# SCH_555-Circuit_2025-03-22_1.net
KiCad netlist of a schematic drawn in EasyEDA
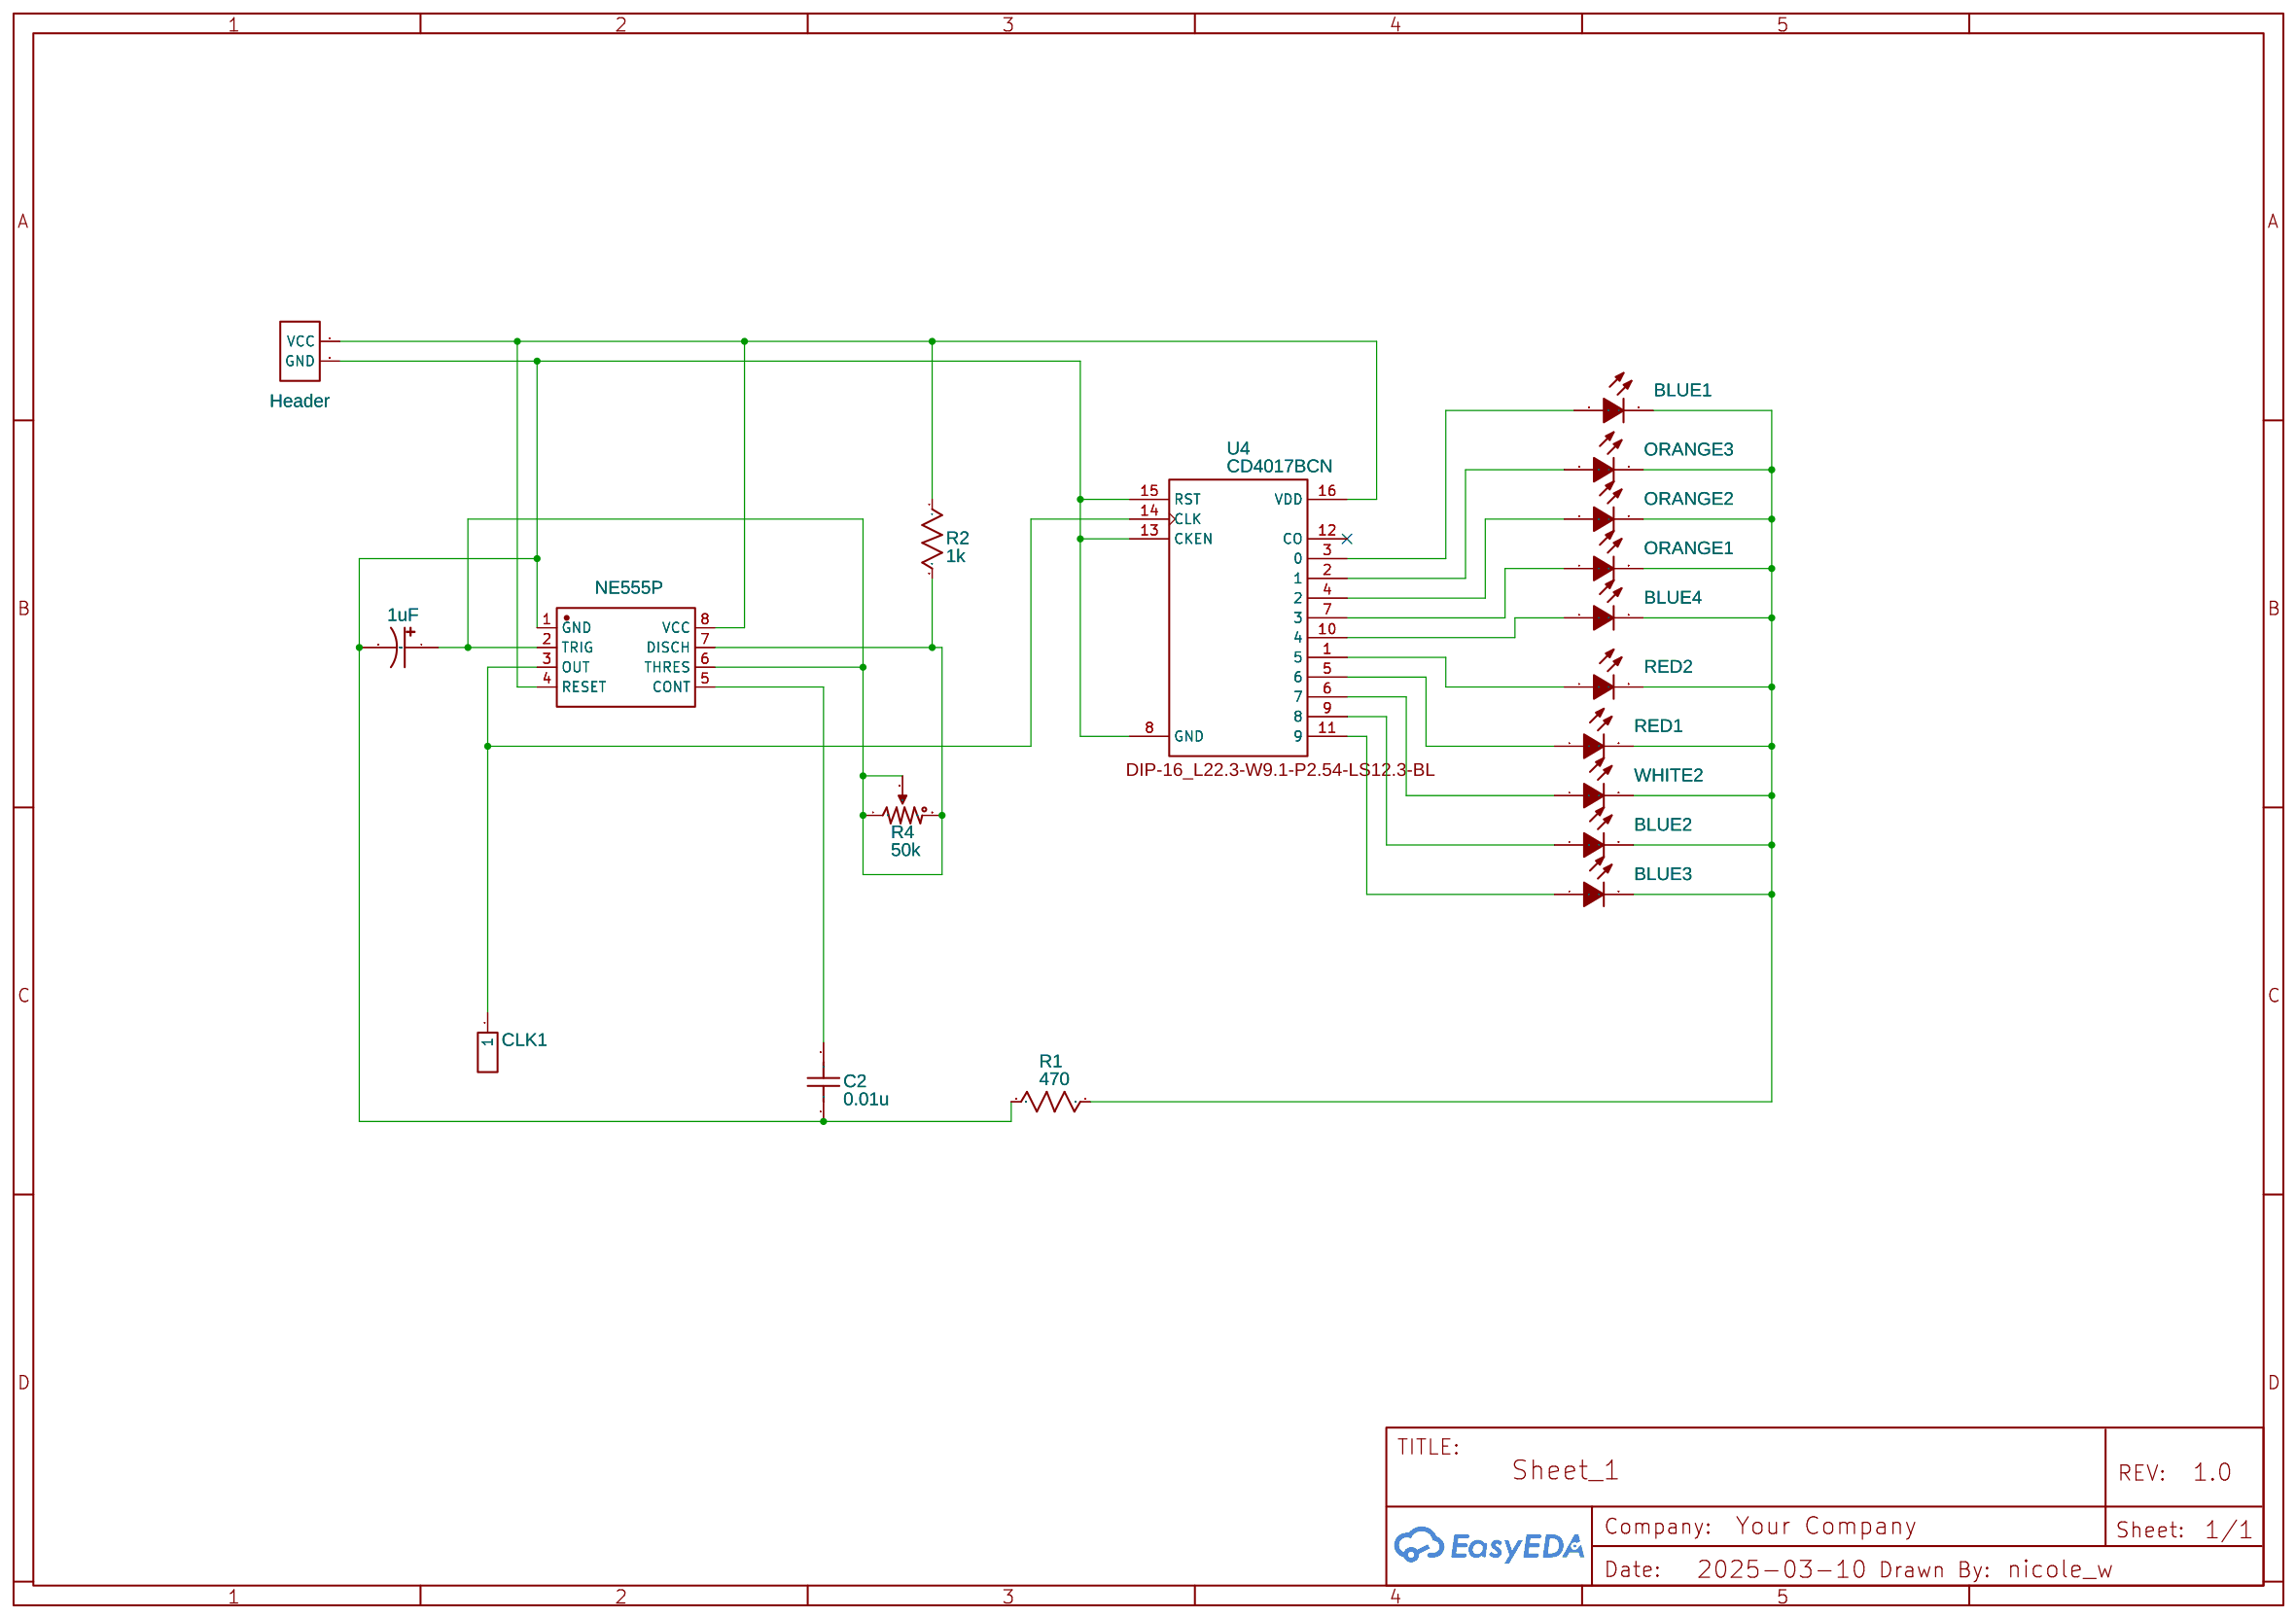
[diagram p0: schematic sheet]

(export (version "E")
  (design (tool "Eeschema 10.0.6"))
  (components
    (comp (ref "BLUE1") (value "LED_5MM") (libsource (lib "") (part "LED_5MM_1")))
    (comp (ref "BLUE2") (value "LED_5MM") (libsource (lib "") (part "LED_5MM_1")))
    (comp (ref "BLUE3") (value "LED_5MM") (libsource (lib "") (part "LED_5MM_1")))
    (comp (ref "BLUE4") (value "LED_5MM") (libsource (lib "") (part "LED_5MM_1")))
    (comp (ref "C1")
      (value "1uF")
      (fields (field (name "Manufacturer Part") "UVZ1H010MDD") (field (name "Manufacturer") "Nichicon(尼吉康)"))
      (libsource (lib "") (part "UVZ1H010MDD"))
    )
    (comp (ref "C2") (value "0.01u") (libsource (lib "") (part "C_0603_US")))
    (comp (ref "CLK1")
      (value "C81276")
      (fields
        (field (name "Manufacturer Part") "2.54-1*1P针")
        (field (name "Manufacturer") "BOOMELE(Boom Precision Elec)")
      )
      (libsource (lib "") (part "Header-Male-2.54_1x1"))
    )
    (comp (ref "H1") (value "Header") (libsource (lib "") (part "HEADER-FEMALE-2.54_1X2")))
    (comp (ref "ORANGE1") (value "LED_5MM") (libsource (lib "") (part "LED_5MM_3")))
    (comp (ref "ORANGE2") (value "LED_5MM") (libsource (lib "") (part "LED_5MM_3")))
    (comp (ref "ORANGE3") (value "LED_5MM") (libsource (lib "") (part "LED_5MM_3")))
    (comp (ref "R1")
      (value "470")
      (fields (field (name "Manufacturer Part") "?"))
      (libsource (lib "") (part "Resistor_1"))
    )
    (comp (ref "R2")
      (value "1k")
      (fields (field (name "Manufacturer Part") "?"))
      (libsource (lib "") (part "Resistor"))
    )
    (comp (ref "R4")
      (value "50k")
      (fields (field (name "Manufacturer Part") "?"))
      (libsource (lib "") (part "Potentiometer"))
    )
    (comp (ref "RED1") (value "LED_5MM") (libsource (lib "") (part "LED_5MM_2")))
    (comp (ref "RED2") (value "LED_5MM") (libsource (lib "") (part "LED_5MM_2")))
    (comp (ref "U2")
      (value "NE555P")
      (fields (field (name "Manufacturer") "TI(德州仪器)"))
      (libsource (lib "") (part "NE555P"))
    )
    (comp (ref "U4") (value "CD4017BCN") (libsource (lib "") (part "CD4017BCN")))
    (comp (ref "WHITE2") (value "LED_5MM") (libsource (lib "") (part "LED_5MM")))
  )
  (nets
    (net (code "1") (name "Net-(BLUE1-A)") (class "Default")
      (node (ref "BLUE1") (pin "1") (pinfunction "A_1") (pintype "input"))
      (node (ref "U4") (pin "3") (pinfunction "0_3") (pintype "output"))
    )
    (net (code "2") (name "Net-(BLUE1-K)") (class "Default")
      (node (ref "BLUE1") (pin "2") (pinfunction "K_2") (pintype "input"))
      (node (ref "BLUE2") (pin "2") (pinfunction "K_2") (pintype "input"))
      (node (ref "BLUE3") (pin "2") (pinfunction "K_2") (pintype "input"))
      (node (ref "BLUE4") (pin "2") (pinfunction "K_2") (pintype "input"))
      (node (ref "ORANGE1") (pin "2") (pinfunction "K_2") (pintype "input"))
      (node (ref "ORANGE2") (pin "2") (pinfunction "K_2") (pintype "input"))
      (node (ref "ORANGE3") (pin "2") (pinfunction "K_2") (pintype "input"))
      (node (ref "R1") (pin "1") (pinfunction "1_1") (pintype "unspecified"))
      (node (ref "RED1") (pin "2") (pinfunction "K_2") (pintype "input"))
      (node (ref "RED2") (pin "2") (pinfunction "K_2") (pintype "input"))
      (node (ref "WHITE2") (pin "2") (pinfunction "K_2") (pintype "input"))
    )
    (net (code "3") (name "Net-(BLUE2-A)") (class "Default")
      (node (ref "BLUE2") (pin "1") (pinfunction "A_1") (pintype "input"))
      (node (ref "U4") (pin "9") (pinfunction "8_9") (pintype "output"))
    )
    (net (code "4") (name "Net-(BLUE3-A)") (class "Default")
      (node (ref "BLUE3") (pin "1") (pinfunction "A_1") (pintype "input"))
      (node (ref "U4") (pin "11") (pinfunction "9_11") (pintype "output"))
    )
    (net (code "5") (name "Net-(BLUE4-A)") (class "Default")
      (node (ref "BLUE4") (pin "1") (pinfunction "A_1") (pintype "input"))
      (node (ref "U4") (pin "10") (pinfunction "4_10") (pintype "output"))
    )
    (net (code "6") (name "Net-(H1-GND)") (class "Default")
      (node (ref "C1") (pin "2") (pinfunction "2_2") (pintype "unspecified"))
      (node (ref "C2") (pin "1") (pinfunction "1_1") (pintype "unspecified"))
      (node (ref "H1") (pin "2") (pinfunction "GND_2") (pintype "unspecified"))
      (node (ref "R1") (pin "2") (pinfunction "2_2") (pintype "unspecified"))
      (node (ref "U2") (pin "1") (pinfunction "GND_1") (pintype "unspecified"))
      (node (ref "U4") (pin "13") (pinfunction "CKEN_13") (pintype "unspecified"))
      (node (ref "U4") (pin "15") (pinfunction "RST_15") (pintype "unspecified"))
      (node (ref "U4") (pin "8") (pinfunction "GND_8") (pintype "passive"))
    )
    (net (code "7") (name "Net-(H1-VCC)") (class "Default")
      (node (ref "H1") (pin "1") (pinfunction "VCC_1") (pintype "unspecified"))
      (node (ref "R2") (pin "1") (pinfunction "1_1") (pintype "unspecified"))
      (node (ref "U2") (pin "4") (pinfunction "RESET_4") (pintype "unspecified"))
      (node (ref "U2") (pin "8") (pinfunction "VCC_8") (pintype "unspecified"))
      (node (ref "U4") (pin "16") (pinfunction "VDD_16") (pintype "passive"))
    )
    (net (code "8") (name "Net-(ORANGE1-A)") (class "Default")
      (node (ref "ORANGE1") (pin "1") (pinfunction "A_1") (pintype "input"))
      (node (ref "U4") (pin "7") (pinfunction "3_7") (pintype "output"))
    )
    (net (code "9") (name "Net-(ORANGE2-A)") (class "Default")
      (node (ref "ORANGE2") (pin "1") (pinfunction "A_1") (pintype "input"))
      (node (ref "U4") (pin "4") (pinfunction "2_4") (pintype "output"))
    )
    (net (code "10") (name "Net-(ORANGE3-A)") (class "Default")
      (node (ref "ORANGE3") (pin "1") (pinfunction "A_1") (pintype "input"))
      (node (ref "U4") (pin "2") (pinfunction "1_2") (pintype "output"))
    )
    (net (code "11") (name "Net-(R4-2)") (class "Default")
      (node (ref "C1") (pin "1") (pinfunction "1_1") (pintype "unspecified"))
      (node (ref "R2") (pin "2") (pinfunction "2_2") (pintype "unspecified"))
      (node (ref "R4") (pin "1") (pinfunction "1_1") (pintype "unspecified"))
      (node (ref "R4") (pin "2") (pinfunction "3_2") (pintype "unspecified"))
      (node (ref "R4") (pin "3") (pinfunction "2_3") (pintype "unspecified"))
      (node (ref "U2") (pin "2") (pinfunction "TRIG_2") (pintype "unspecified"))
      (node (ref "U2") (pin "6") (pinfunction "THRES_6") (pintype "unspecified"))
      (node (ref "U2") (pin "7") (pinfunction "DISCH_7") (pintype "unspecified"))
    )
    (net (code "12") (name "Net-(RED1-A)") (class "Default")
      (node (ref "RED1") (pin "1") (pinfunction "A_1") (pintype "input"))
      (node (ref "U4") (pin "5") (pinfunction "6_5") (pintype "output"))
    )
    (net (code "13") (name "Net-(RED2-A)") (class "Default")
      (node (ref "RED2") (pin "1") (pinfunction "A_1") (pintype "input"))
      (node (ref "U4") (pin "1") (pinfunction "5_1") (pintype "output"))
    )
    (net (code "14") (name "Net-(U2-CONT)") (class "Default")
      (node (ref "C2") (pin "2") (pinfunction "2_2") (pintype "unspecified"))
      (node (ref "U2") (pin "5") (pinfunction "CONT_5") (pintype "unspecified"))
    )
    (net (code "15") (name "Net-(U2-OUT)") (class "Default")
      (node (ref "CLK1") (pin "1") (pinfunction "1_1") (pintype "unspecified"))
      (node (ref "U2") (pin "3") (pinfunction "OUT_3") (pintype "unspecified"))
      (node (ref "U4") (pin "14") (pinfunction "CLK_14") (pintype "unspecified"))
    )
    (net (code "16") (name "Net-(U4-7)") (class "Default")
      (node (ref "U4") (pin "6") (pinfunction "7_6") (pintype "output"))
      (node (ref "WHITE2") (pin "1") (pinfunction "A_1") (pintype "input"))
    )
    (net (code "17") (name "unconnected-(U4-CO-Pad12)") (class "Default")
      (node (ref "U4") (pin "12") (pinfunction "CO_12") (pintype "output+no_connect"))
    )
  )
)
